# attiny85_bo_1l.net
KiCad netlist of a schematic drawn in EAGLE
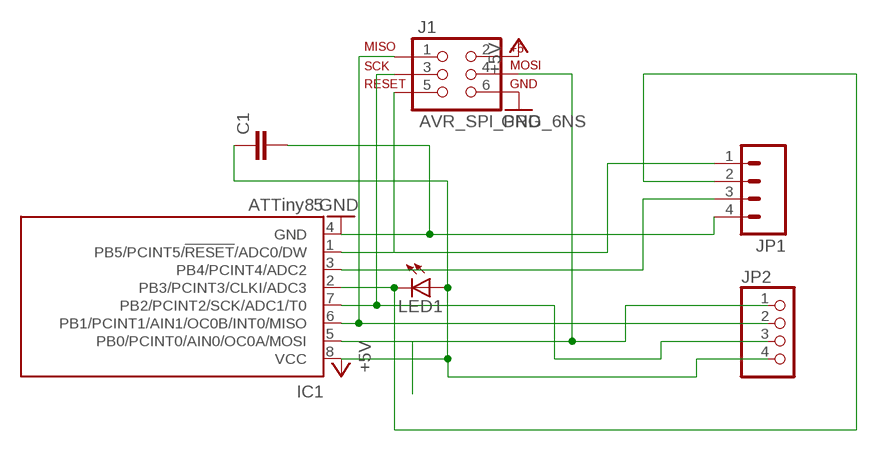
[diagram p0: schematic, sheet 1]

(export (version "E")
  (design (tool "Eeschema 10.0.6"))
  (components
    (comp (ref "C1")
      (value "C-EUC0805")
      (footprint "eagle-import:C0805")
      (libsource (lib "eagle-import") (part "C-EUC0805"))
    )
    (comp (ref "IC1")
      (value "ATTiny85")
      (footprint "eagle-import:8S2")
      (fields (field (name "MPN") "ATTINY13-20SU"))
      (libsource (lib "eagle-import") (part "TINY13SU-20"))
    )
    (comp (ref "J1")
      (value "AVR_SPI_PRG_6NS")
      (footprint "eagle-import:2X3-NS")
      (libsource (lib "eagle-import") (part "AVR_SPI_PRG_6NS"))
    )
    (comp (ref "JP1")
      (value "M041X04_NO_SILK")
      (footprint "eagle-import:1X04_NO_SILK")
      (libsource (lib "eagle-import") (part "M041X04_NO_SILK"))
    )
    (comp (ref "JP2")
      (value "PINHD-1X4")
      (footprint "eagle-import:1X04")
      (libsource (lib "eagle-import") (part "PINHD-1X4"))
    )
    (comp (ref "LED1")
      (value "LED0603")
      (footprint "eagle-import:LED-0603")
      (libsource (lib "eagle-import") (part "LED0603"))
    )
  )
  (nets
    (net (code "1") (name "+5V") (class "Default")
      (node (ref "C1") (pin "1") (pinfunction "1_1") (pintype "passive"))
      (node (ref "IC1") (pin "8") (pinfunction "VCC_8") (pintype "power_in"))
      (node (ref "J1") (pin "2") (pinfunction "2_2") (pintype "passive"))
      (node (ref "JP2") (pin "4") (pinfunction "4_4") (pintype "passive"))
      (node (ref "LED1") (pin "A") (pinfunction "A_A") (pintype "passive"))
    )
    (net (code "2") (name "GND") (class "Default")
      (node (ref "C1") (pin "2") (pinfunction "2_2") (pintype "passive"))
      (node (ref "IC1") (pin "4") (pinfunction "GND_4") (pintype "power_in"))
      (node (ref "J1") (pin "6") (pinfunction "6_6") (pintype "passive"))
      (node (ref "JP1") (pin "4") (pinfunction "4_4") (pintype "passive"))
    )
    (net (code "3") (name "Net-(IC1-PB0{slash}PCINT0{slash}AIN0{slash}OC0A{slash}MOSI)") (class "Default")
      (node (ref "IC1") (pin "5") (pinfunction "PB0/PCINT0/AIN0/OC0A/MOSI_5") (pintype "bidirectional"))
      (node (ref "J1") (pin "4") (pinfunction "4_4") (pintype "passive"))
      (node (ref "JP2") (pin "1") (pinfunction "1_1") (pintype "passive"))
    )
    (net (code "4") (name "Net-(IC1-PB1{slash}PCINT1{slash}AIN1{slash}OC0B{slash}INT0{slash}MISO)") (class "Default")
      (node (ref "IC1") (pin "6") (pinfunction "PB1/PCINT1/AIN1/OC0B/INT0/MISO_6") (pintype "bidirectional"))
      (node (ref "J1") (pin "1") (pinfunction "1_1") (pintype "passive"))
      (node (ref "JP2") (pin "2") (pinfunction "2_2") (pintype "passive"))
    )
    (net (code "5") (name "Net-(IC1-PB2{slash}PCINT2{slash}SCK{slash}ADC1{slash}T0)") (class "Default")
      (node (ref "IC1") (pin "7") (pinfunction "PB2/PCINT2/SCK/ADC1/T0_7") (pintype "bidirectional"))
      (node (ref "J1") (pin "3") (pinfunction "3_3") (pintype "passive"))
      (node (ref "JP2") (pin "3") (pinfunction "3_3") (pintype "passive"))
    )
    (net (code "6") (name "Net-(IC1-PB3{slash}PCINT3{slash}CLKI{slash}ADC3)") (class "Default")
      (node (ref "IC1") (pin "2") (pinfunction "PB3/PCINT3/CLKI/ADC3_2") (pintype "bidirectional"))
      (node (ref "JP1") (pin "2") (pinfunction "2_2") (pintype "passive"))
      (node (ref "LED1") (pin "C") (pinfunction "C_C") (pintype "passive"))
    )
    (net (code "7") (name "Net-(IC1-PB4{slash}PCINT4{slash}ADC2)") (class "Default")
      (node (ref "IC1") (pin "3") (pinfunction "PB4/PCINT4/ADC2_3") (pintype "bidirectional"))
      (node (ref "JP1") (pin "3") (pinfunction "3_3") (pintype "passive"))
    )
    (net (code "8") (name "Net-(IC1-PB5{slash}PCINT5{slash}~{RESET}{slash}ADC0{slash}DW)") (class "Default")
      (node (ref "IC1") (pin "1") (pinfunction "PB5/PCINT5/~{RESET}/ADC0/DW_1") (pintype "bidirectional"))
      (node (ref "J1") (pin "5") (pinfunction "5_5") (pintype "passive"))
      (node (ref "JP1") (pin "1") (pinfunction "1_1") (pintype "passive"))
    )
  )
)
